# SixPotatoeV4.net
KiCad netlist of a schematic drawn in EAGLE
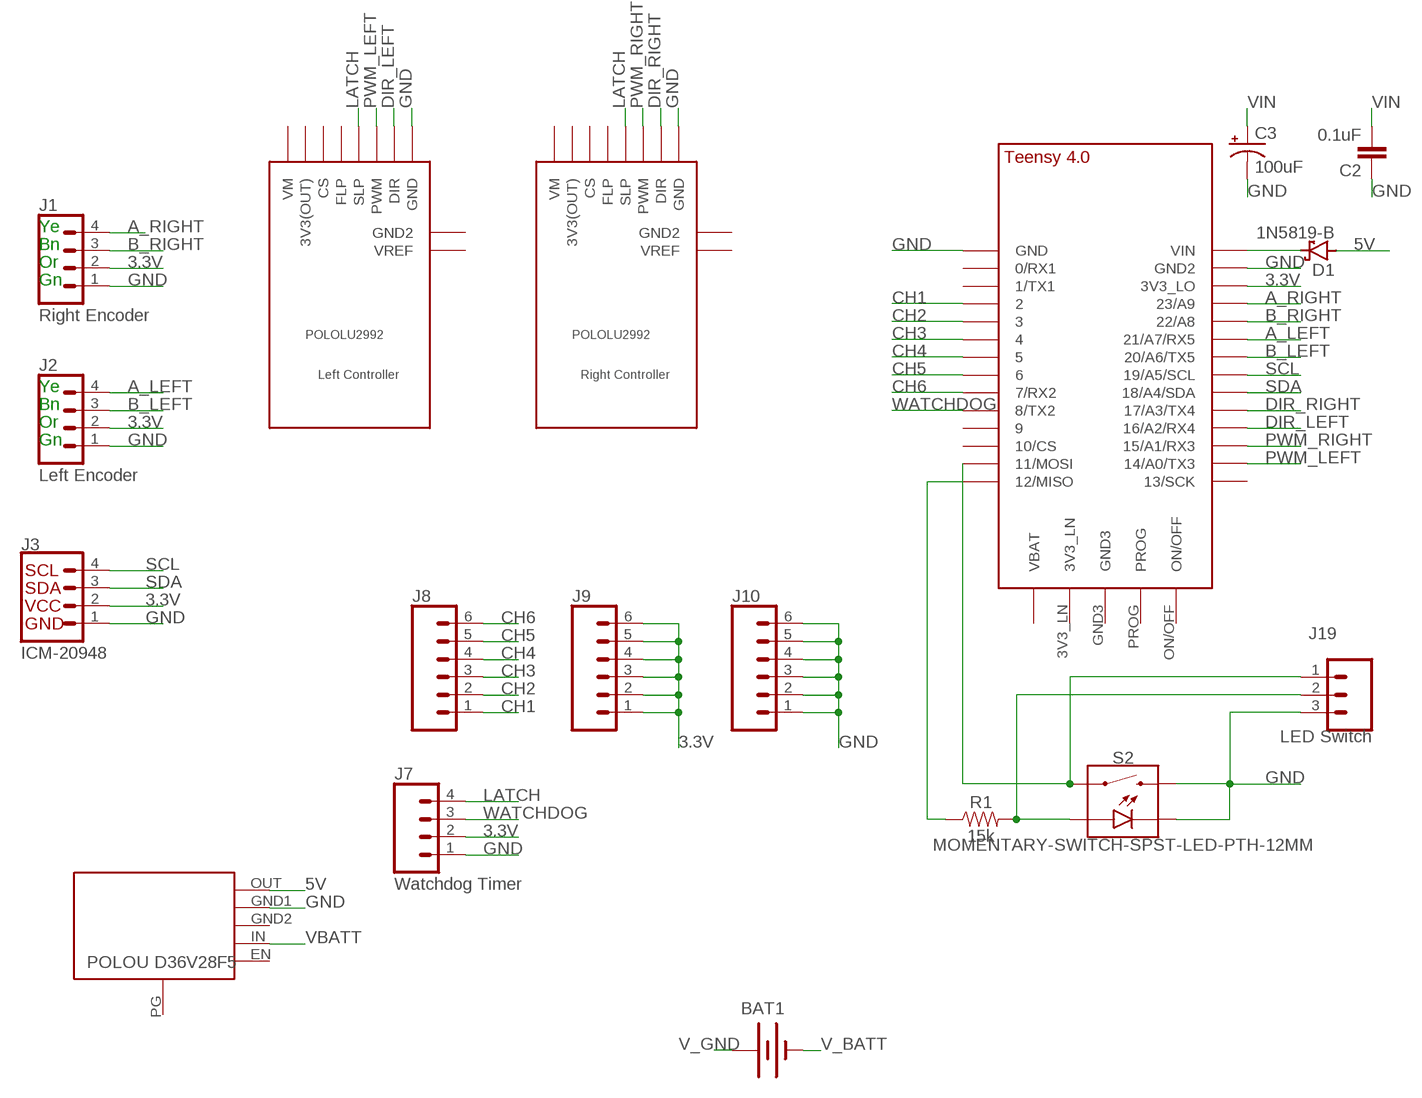
[diagram p0: schematic, sheet 1]

(export (version "E")
  (design (tool "Eeschema 10.0.6"))
  (components
    (comp (ref "BAT1")
      (value "XT60_MALE")
      (footprint "eagle-import:XT60")
      (libsource (lib "eagle-import") (part "XT60_MALE"))
    )
    (comp (ref "C2")
      (value "0.1uF")
      (footprint "eagle-import:CAP-PTH-SMALL-KIT")
      (libsource (lib "eagle-import") (part "0.1UF-KIT-EZ-50V-20%"))
    )
    (comp (ref "C3")
      (value "100uF")
      (footprint "eagle-import:CPOL-RADIAL-2.5MM-6.5MM")
      (libsource (lib "eagle-import") (part "100UF-POLAR-RADIAL-2.5MM-25V-20%"))
    )
    (comp (ref "D1")
      (value "1N5819-B")
      (footprint "eagle-import:DO41-7.6")
      (libsource (lib "eagle-import") (part "1N5819-B"))
    )
    (comp (ref "J1")
      (value "CONN_04")
      (footprint "eagle-import:1X04")
      (fields (field (name "ID") "Right Encoder"))
      (libsource (lib "eagle-import") (part "CONN_04"))
    )
    (comp (ref "J2")
      (value "CONN_04")
      (footprint "eagle-import:1X04")
      (fields (field (name "ID") "Left Encoder"))
      (libsource (lib "eagle-import") (part "CONN_04"))
    )
    (comp (ref "J3")
      (value "I2C_STANDARD")
      (footprint "eagle-import:1X04")
      (fields (field (name "ID") "ICM-20948"))
      (libsource (lib "eagle-import") (part "I2C_STANDARD"))
    )
    (comp (ref "J7")
      (value "CONN_04")
      (footprint "eagle-import:1X04")
      (fields (field (name "ID") "Watchdog Timer"))
      (libsource (lib "eagle-import") (part "CONN_04"))
    )
    (comp (ref "J8")
      (value "CONN_06NO_SILK_FEMALE_PTH")
      (footprint "eagle-import:1X06_NO_SILK")
      (libsource (lib "eagle-import") (part "CONN_06NO_SILK_FEMALE_PTH"))
    )
    (comp (ref "J9")
      (value "CONN_06NO_SILK_FEMALE_PTH")
      (footprint "eagle-import:1X06_NO_SILK")
      (libsource (lib "eagle-import") (part "CONN_06NO_SILK_FEMALE_PTH"))
    )
    (comp (ref "J10")
      (value "CONN_06NO_SILK_FEMALE_PTH")
      (footprint "eagle-import:1X06_NO_SILK")
      (libsource (lib "eagle-import") (part "CONN_06NO_SILK_FEMALE_PTH"))
    )
    (comp (ref "J19")
      (value "CONN_03")
      (footprint "eagle-import:1X03")
      (fields (field (name "ID") "LED Switch"))
      (libsource (lib "eagle-import") (part "CONN_03"))
    )
    (comp (ref "R1")
      (value "15k")
      (footprint "eagle-import:AXIAL-0.3")
      (libsource (lib "eagle-import") (part "15KOHM-HORIZ-1/4W-5%"))
    )
    (comp (ref "S2")
      (value "MOMENTARY-SWITCH-SPST-LED-PTH-12MM")
      (footprint "eagle-import:TACTILE_SWITCH_LED_PTH_12MM")
      (libsource (lib "eagle-import") (part "MOMENTARY-SWITCH-SPST-LED-PTH-12MM"))
    )
    (comp (ref "U$1")
      (value "TEENSY_4.0")
      (footprint "eagle-import:TEENSY_4.0")
      (libsource (lib "eagle-import") (part "TEENSY_4.0"))
    )
    (comp (ref "U$2")
      (value "Left Controller")
      (footprint "eagle-import:POLOLU2992_2")
      (libsource (lib "eagle-import") (part "POLOLU2992_2"))
    )
    (comp (ref "U$3")
      (value "Right Controller")
      (footprint "eagle-import:POLOLU2992_2")
      (libsource (lib "eagle-import") (part "POLOLU2992_2"))
    )
    (comp (ref "U$4")
      (value "POLOU3782")
      (footprint "eagle-import:POLOU3782")
      (libsource (lib "eagle-import") (part "POLOU3782"))
    )
  )
  (nets
    (net (code "1") (name "/3.3V") (class "Default")
      (node (ref "J1") (pin "2") (pinfunction "2_2") (pintype "passive"))
      (node (ref "J2") (pin "2") (pinfunction "2_2") (pintype "passive"))
      (node (ref "J3") (pin "2") (pinfunction "2_2") (pintype "power_in"))
      (node (ref "J7") (pin "2") (pinfunction "2_2") (pintype "passive"))
      (node (ref "J9") (pin "1") (pinfunction "1_1") (pintype "passive"))
      (node (ref "J9") (pin "2") (pinfunction "2_2") (pintype "passive"))
      (node (ref "J9") (pin "3") (pinfunction "3_3") (pintype "passive"))
      (node (ref "J9") (pin "4") (pinfunction "4_4") (pintype "passive"))
      (node (ref "J9") (pin "5") (pinfunction "5_5") (pintype "passive"))
      (node (ref "J9") (pin "6") (pinfunction "6_6") (pintype "passive"))
      (node (ref "U$1") (pin "3V3_LO") (pinfunction "3V3_LO_3V3_LO") (pintype "bidirectional"))
    )
    (net (code "2") (name "/5V") (class "Default")
      (node (ref "D1") (pin "A") (pinfunction "A_A") (pintype "passive"))
      (node (ref "U$4") (pin "OUT") (pinfunction "OUT_OUT") (pintype "bidirectional"))
    )
    (net (code "3") (name "/A_LEFT") (class "Default")
      (node (ref "J2") (pin "4") (pinfunction "4_4") (pintype "passive"))
      (node (ref "U$1") (pin "21/A7") (pinfunction "21/A7/RX5_21/A7") (pintype "bidirectional"))
    )
    (net (code "4") (name "/A_RIGHT") (class "Default")
      (node (ref "J1") (pin "4") (pinfunction "4_4") (pintype "passive"))
      (node (ref "U$1") (pin "23/A9") (pinfunction "23/A9_23/A9") (pintype "bidirectional"))
    )
    (net (code "5") (name "/B_LEFT") (class "Default")
      (node (ref "J2") (pin "3") (pinfunction "3_3") (pintype "passive"))
      (node (ref "U$1") (pin "20/A6") (pinfunction "20/A6/TX5_20/A6") (pintype "bidirectional"))
    )
    (net (code "6") (name "/B_RIGHT") (class "Default")
      (node (ref "J1") (pin "3") (pinfunction "3_3") (pintype "passive"))
      (node (ref "U$1") (pin "22/A8") (pinfunction "22/A8_22/A8") (pintype "bidirectional"))
    )
    (net (code "7") (name "/CH1") (class "Default")
      (node (ref "J8") (pin "1") (pinfunction "1_1") (pintype "passive"))
      (node (ref "U$1") (pin "2") (pinfunction "2_2") (pintype "bidirectional"))
    )
    (net (code "8") (name "/CH2") (class "Default")
      (node (ref "J8") (pin "2") (pinfunction "2_2") (pintype "passive"))
      (node (ref "U$1") (pin "3/CANTX") (pinfunction "3_3/CANTX") (pintype "bidirectional"))
    )
    (net (code "9") (name "/CH3") (class "Default")
      (node (ref "J8") (pin "3") (pinfunction "3_3") (pintype "passive"))
      (node (ref "U$1") (pin "4/CANRX") (pinfunction "4_4/CANRX") (pintype "bidirectional"))
    )
    (net (code "10") (name "/CH4") (class "Default")
      (node (ref "J8") (pin "4") (pinfunction "4_4") (pintype "passive"))
      (node (ref "U$1") (pin "5") (pinfunction "5_5") (pintype "bidirectional"))
    )
    (net (code "11") (name "/CH5") (class "Default")
      (node (ref "J8") (pin "5") (pinfunction "5_5") (pintype "passive"))
      (node (ref "U$1") (pin "6") (pinfunction "6_6") (pintype "bidirectional"))
    )
    (net (code "12") (name "/CH6") (class "Default")
      (node (ref "J8") (pin "6") (pinfunction "6_6") (pintype "passive"))
      (node (ref "U$1") (pin "7") (pinfunction "7/RX2_7") (pintype "bidirectional"))
    )
    (net (code "13") (name "/DIR_LEFT") (class "Default")
      (node (ref "U$1") (pin "16/A2") (pinfunction "16/A2/RX4_16/A2") (pintype "bidirectional"))
      (node (ref "U$2") (pin "DIR") (pinfunction "DIR_DIR") (pintype "bidirectional"))
    )
    (net (code "14") (name "/DIR_RIGHT") (class "Default")
      (node (ref "U$1") (pin "17/A3") (pinfunction "17/A3/TX4_17/A3") (pintype "bidirectional"))
      (node (ref "U$3") (pin "DIR") (pinfunction "DIR_DIR") (pintype "bidirectional"))
    )
    (net (code "15") (name "/GND") (class "Default")
      (node (ref "C2") (pin "1") (pinfunction "1_1") (pintype "passive"))
      (node (ref "C3") (pin "2") (pinfunction "-_2") (pintype "passive"))
      (node (ref "J1") (pin "1") (pinfunction "1_1") (pintype "passive"))
      (node (ref "J10") (pin "1") (pinfunction "1_1") (pintype "passive"))
      (node (ref "J10") (pin "2") (pinfunction "2_2") (pintype "passive"))
      (node (ref "J10") (pin "3") (pinfunction "3_3") (pintype "passive"))
      (node (ref "J10") (pin "4") (pinfunction "4_4") (pintype "passive"))
      (node (ref "J10") (pin "5") (pinfunction "5_5") (pintype "passive"))
      (node (ref "J10") (pin "6") (pinfunction "6_6") (pintype "passive"))
      (node (ref "J19") (pin "3") (pinfunction "3_3") (pintype "passive"))
      (node (ref "J2") (pin "1") (pinfunction "1_1") (pintype "passive"))
      (node (ref "J3") (pin "1") (pinfunction "1_1") (pintype "power_in"))
      (node (ref "J7") (pin "1") (pinfunction "1_1") (pintype "passive"))
      (node (ref "S2") (pin "2") (pinfunction "2_2") (pintype "passive"))
      (node (ref "S2") (pin "C") (pinfunction "C_C") (pintype "passive"))
      (node (ref "U$1") (pin "GND") (pinfunction "GND_GND") (pintype "bidirectional"))
      (node (ref "U$1") (pin "GND2") (pinfunction "GND2_GND2") (pintype "bidirectional"))
      (node (ref "U$2") (pin "GND") (pinfunction "GND_GND") (pintype "bidirectional"))
      (node (ref "U$3") (pin "GND") (pinfunction "GND_GND") (pintype "bidirectional"))
      (node (ref "U$4") (pin "GND1") (pinfunction "GND1_GND1") (pintype "bidirectional"))
    )
    (net (code "16") (name "/LATCH") (class "Default")
      (node (ref "J7") (pin "4") (pinfunction "4_4") (pintype "passive"))
      (node (ref "U$2") (pin "SLP") (pinfunction "SLP_SLP") (pintype "bidirectional"))
      (node (ref "U$3") (pin "SLP") (pinfunction "SLP_SLP") (pintype "bidirectional"))
    )
    (net (code "17") (name "/PWM_LEFT") (class "Default")
      (node (ref "U$1") (pin "14/A0") (pinfunction "14/A0/TX3_14/A0") (pintype "bidirectional"))
      (node (ref "U$2") (pin "PWM") (pinfunction "PWM_PWM") (pintype "bidirectional"))
    )
    (net (code "18") (name "/PWM_RIGHT") (class "Default")
      (node (ref "U$1") (pin "15/A1") (pinfunction "15/A1/RX3_15/A1") (pintype "bidirectional"))
      (node (ref "U$3") (pin "PWM") (pinfunction "PWM_PWM") (pintype "bidirectional"))
    )
    (net (code "19") (name "/SCL") (class "Default")
      (node (ref "J3") (pin "4") (pinfunction "4_4") (pintype "passive"))
      (node (ref "U$1") (pin "19/A5/SCL") (pinfunction "19/A5/SCL_19/A5/SCL") (pintype "bidirectional"))
    )
    (net (code "20") (name "/SDA") (class "Default")
      (node (ref "J3") (pin "3") (pinfunction "3_3") (pintype "passive"))
      (node (ref "U$1") (pin "18/A4/SDA") (pinfunction "18/A4/SDA_18/A4/SDA") (pintype "bidirectional"))
    )
    (net (code "21") (name "/VBATT") (class "Default")
      (node (ref "U$4") (pin "IN") (pinfunction "IN_IN") (pintype "bidirectional"))
    )
    (net (code "22") (name "/VIN") (class "Default")
      (node (ref "C2") (pin "2") (pinfunction "2_2") (pintype "passive"))
      (node (ref "C3") (pin "1") (pinfunction "+_1") (pintype "passive"))
    )
    (net (code "23") (name "/V_BATT") (class "Default")
      (node (ref "BAT1") (pin "-") (pinfunction "-_-") (pintype "power_in"))
    )
    (net (code "24") (name "/V_GND") (class "Default")
      (node (ref "BAT1") (pin "+") (pinfunction "+_+") (pintype "power_in"))
    )
    (net (code "25") (name "/WATCHDOG") (class "Default")
      (node (ref "J7") (pin "3") (pinfunction "3_3") (pintype "passive"))
      (node (ref "U$1") (pin "8") (pinfunction "8/TX2_8") (pintype "bidirectional"))
    )
    (net (code "26") (name "Net-(D1-PadC)") (class "Default")
      (node (ref "D1") (pin "C") (pinfunction "C_C") (pintype "passive"))
      (node (ref "U$1") (pin "VIN") (pinfunction "VIN_VIN") (pintype "bidirectional"))
    )
    (net (code "27") (name "Net-(R1-1)") (class "Default")
      (node (ref "R1") (pin "P$1") (pinfunction "1_P$1") (pintype "passive"))
      (node (ref "U$1") (pin "12/MISO") (pinfunction "12/MISO_12/MISO") (pintype "bidirectional"))
    )
    (net (code "28") (name "Net-(R1-2)") (class "Default")
      (node (ref "J19") (pin "2") (pinfunction "2_2") (pintype "passive"))
      (node (ref "R1") (pin "P$2") (pinfunction "2_P$2") (pintype "passive"))
      (node (ref "S2") (pin "A") (pinfunction "A_A") (pintype "passive"))
    )
    (net (code "29") (name "Net-(S2-1)") (class "Default")
      (node (ref "J19") (pin "1") (pinfunction "1_1") (pintype "passive"))
      (node (ref "S2") (pin "4") (pinfunction "1_4") (pintype "passive"))
      (node (ref "U$1") (pin "11/MOSI") (pinfunction "11/MOSI_11/MOSI") (pintype "bidirectional"))
    )
    (net (code "30") (name "unconnected-(U$1-0{slash}RX1-Pad0{slash}RX)") (class "Default")
      (node (ref "U$1") (pin "0/RX") (pinfunction "0/RX1_0/RX") (pintype "bidirectional"))
    )
    (net (code "31") (name "unconnected-(U$1-1{slash}TX1-Pad1{slash}TX)") (class "Default")
      (node (ref "U$1") (pin "1/TX") (pinfunction "1/TX1_1/TX") (pintype "bidirectional"))
    )
    (net (code "32") (name "unconnected-(U$1-9-Pad9{slash}CS)") (class "Default")
      (node (ref "U$1") (pin "9/CS") (pinfunction "9_9/CS") (pintype "bidirectional"))
    )
    (net (code "33") (name "unconnected-(U$1-Pad3V3_LN)") (class "Default")
      (node (ref "U$1") (pin "3V3_LN") (pinfunction "3V3_LN_3V3_LN") (pintype "bidirectional"))
    )
    (net (code "34") (name "unconnected-(U$1-Pad10{slash}CS)") (class "Default")
      (node (ref "U$1") (pin "10/CS") (pinfunction "10/CS_10/CS") (pintype "bidirectional"))
    )
    (net (code "35") (name "unconnected-(U$1-Pad13{slash}SCK)") (class "Default")
      (node (ref "U$1") (pin "13/SCK") (pinfunction "13/SCK_13/SCK") (pintype "bidirectional"))
    )
    (net (code "36") (name "unconnected-(U$1-PadGND3)") (class "Default")
      (node (ref "U$1") (pin "GND3") (pinfunction "GND3_GND3") (pintype "bidirectional"))
    )
    (net (code "37") (name "unconnected-(U$1-PadON{slash}OFF)") (class "Default")
      (node (ref "U$1") (pin "ON/OFF") (pinfunction "ON/OFF_ON/OFF") (pintype "bidirectional"))
    )
    (net (code "38") (name "unconnected-(U$1-PadPROG)") (class "Default")
      (node (ref "U$1") (pin "PROG") (pinfunction "PROG_PROG") (pintype "bidirectional"))
    )
    (net (code "39") (name "unconnected-(U$1-VBAT-PadVBAT\\)") (class "Default")
      (node (ref "U$1") (pin "VBAT\\") (pinfunction "VBAT_VBAT\\") (pintype "bidirectional"))
    )
    (net (code "40") (name "unconnected-(U$2-Pad3V3(OUT))") (class "Default")
      (node (ref "U$2") (pin "3V3(OUT)") (pinfunction "3V3(OUT)_3V3(OUT)") (pintype "bidirectional"))
    )
    (net (code "41") (name "unconnected-(U$2-PadCS)") (class "Default")
      (node (ref "U$2") (pin "CS") (pinfunction "CS_CS") (pintype "bidirectional"))
    )
    (net (code "42") (name "unconnected-(U$2-PadFLP)") (class "Default")
      (node (ref "U$2") (pin "FLP") (pinfunction "FLP_FLP") (pintype "bidirectional"))
    )
    (net (code "43") (name "unconnected-(U$2-PadGND2)") (class "Default")
      (node (ref "U$2") (pin "GND2") (pinfunction "GND2_GND2") (pintype "bidirectional"))
    )
    (net (code "44") (name "unconnected-(U$2-PadVM)") (class "Default")
      (node (ref "U$2") (pin "VM") (pinfunction "VM_VM") (pintype "bidirectional"))
    )
    (net (code "45") (name "unconnected-(U$2-PadVREF)") (class "Default")
      (node (ref "U$2") (pin "VREF") (pinfunction "VREF_VREF") (pintype "bidirectional"))
    )
    (net (code "46") (name "unconnected-(U$3-Pad3V3(OUT))") (class "Default")
      (node (ref "U$3") (pin "3V3(OUT)") (pinfunction "3V3(OUT)_3V3(OUT)") (pintype "bidirectional"))
    )
    (net (code "47") (name "unconnected-(U$3-PadCS)") (class "Default")
      (node (ref "U$3") (pin "CS") (pinfunction "CS_CS") (pintype "bidirectional"))
    )
    (net (code "48") (name "unconnected-(U$3-PadFLP)") (class "Default")
      (node (ref "U$3") (pin "FLP") (pinfunction "FLP_FLP") (pintype "bidirectional"))
    )
    (net (code "49") (name "unconnected-(U$3-PadGND2)") (class "Default")
      (node (ref "U$3") (pin "GND2") (pinfunction "GND2_GND2") (pintype "bidirectional"))
    )
    (net (code "50") (name "unconnected-(U$3-PadVM)") (class "Default")
      (node (ref "U$3") (pin "VM") (pinfunction "VM_VM") (pintype "bidirectional"))
    )
    (net (code "51") (name "unconnected-(U$3-PadVREF)") (class "Default")
      (node (ref "U$3") (pin "VREF") (pinfunction "VREF_VREF") (pintype "bidirectional"))
    )
    (net (code "52") (name "unconnected-(U$4-PadEN)") (class "Default")
      (node (ref "U$4") (pin "EN") (pinfunction "EN_EN") (pintype "bidirectional"))
    )
    (net (code "53") (name "unconnected-(U$4-PadGND2)") (class "Default")
      (node (ref "U$4") (pin "GND2") (pinfunction "GND2_GND2") (pintype "bidirectional"))
    )
    (net (code "54") (name "unconnected-(U$4-PadPG)") (class "Default")
      (node (ref "U$4") (pin "PG") (pinfunction "PG_PG") (pintype "bidirectional"))
    )
  )
)
